# NE555_Variable_Frequency_Oscillator_with.net
KiCad netlist of a schematic drawn in EAGLE
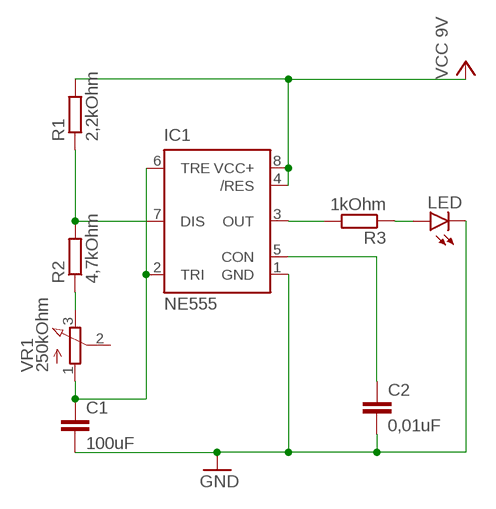
[diagram p0: schematic, sheet 1]

(export (version "E")
  (design (tool "Eeschema 10.0.6"))
  (components
    (comp (ref "C1")
      (value "100uF")
      (footprint "eagle-import:C2.5-3")
      (libsource (lib "eagle-import") (part "C2,5-3"))
    )
    (comp (ref "C2")
      (value "0,01uF")
      (footprint "eagle-import:C2.5-3")
      (libsource (lib "eagle-import") (part "C2,5-3"))
    )
    (comp (ref "IC1")
      (value "NE555")
      (footprint "eagle-import:DIL-08")
      (fields (field (name "MF") "Arrow Electronics") (field (name "MPN") "NE555N"))
      (libsource (lib "eagle-import") (part "NE555"))
    )
    (comp (ref "LED")
      (value "LED5MM")
      (footprint "eagle-import:LED5MM")
      (libsource (lib "eagle-import") (part "LED5MM"))
    )
    (comp (ref "R1")
      (value "2,2kOhm")
      (footprint "eagle-import:0204V")
      (libsource (lib "eagle-import") (part "R-EU_0204/2V"))
    )
    (comp (ref "R2")
      (value "4,7kOhm")
      (footprint "eagle-import:0204V")
      (libsource (lib "eagle-import") (part "R-EU_0204/2V"))
    )
    (comp (ref "R3")
      (value "1kOhm")
      (footprint "eagle-import:0204V")
      (libsource (lib "eagle-import") (part "R-EU_0204/2V"))
    )
    (comp (ref "VR1")
      (value "250kOhm")
      (footprint "eagle-import:3RP_1610N")
      (libsource (lib "eagle-import") (part "3RP/1610N"))
    )
  )
  (nets
    (net (code "1") (name "GND") (class "Default")
      (node (ref "C1") (pin "2") (pinfunction "2_2") (pintype "passive"))
      (node (ref "C2") (pin "2") (pinfunction "2_2") (pintype "passive"))
      (node (ref "IC1") (pin "1") (pinfunction "GND_1") (pintype "power_in"))
      (node (ref "LED") (pin "K") (pinfunction "C_K") (pintype "passive"))
    )
    (net (code "2") (name "Net-(IC1-CON)") (class "Default")
      (node (ref "C2") (pin "1") (pinfunction "1_1") (pintype "passive"))
      (node (ref "IC1") (pin "5") (pinfunction "CON_5") (pintype "input"))
    )
    (net (code "3") (name "Net-(IC1-DIS)") (class "Default")
      (node (ref "IC1") (pin "7") (pinfunction "DIS_7") (pintype "input"))
      (node (ref "R1") (pin "1") (pinfunction "1_1") (pintype "passive"))
      (node (ref "R2") (pin "2") (pinfunction "2_2") (pintype "passive"))
    )
    (net (code "4") (name "Net-(IC1-OUT)") (class "Default")
      (node (ref "IC1") (pin "3") (pinfunction "OUT_3") (pintype "output"))
      (node (ref "R3") (pin "2") (pinfunction "2_2") (pintype "passive"))
    )
    (net (code "5") (name "Net-(IC1-TRE)") (class "Default")
      (node (ref "C1") (pin "1") (pinfunction "1_1") (pintype "passive"))
      (node (ref "IC1") (pin "2") (pinfunction "TRI_2") (pintype "input"))
      (node (ref "IC1") (pin "6") (pinfunction "TRE_6") (pintype "input"))
      (node (ref "VR1") (pin "1") (pinfunction "A_1") (pintype "passive"))
    )
    (net (code "6") (name "Net-(LED-PadA)") (class "Default")
      (node (ref "LED") (pin "A") (pinfunction "A_A") (pintype "passive"))
      (node (ref "R3") (pin "1") (pinfunction "1_1") (pintype "passive"))
    )
    (net (code "7") (name "Net-(VR1-E)") (class "Default")
      (node (ref "R2") (pin "1") (pinfunction "1_1") (pintype "passive"))
      (node (ref "VR1") (pin "3") (pinfunction "E_3") (pintype "passive"))
    )
    (net (code "8") (name "VCC 9V") (class "Default")
      (node (ref "IC1") (pin "4") (pinfunction "/RES_4") (pintype "input"))
      (node (ref "IC1") (pin "8") (pinfunction "VCC+_8") (pintype "power_in"))
      (node (ref "R1") (pin "2") (pinfunction "2_2") (pintype "passive"))
    )
    (net (code "9") (name "unconnected-(VR1-S-Pad2)") (class "Default")
      (node (ref "VR1") (pin "2") (pinfunction "S_2") (pintype "passive"))
    )
  )
)
